# Schematic_of_7_syringe_pump.net
KiCad netlist of a schematic drawn in EAGLE
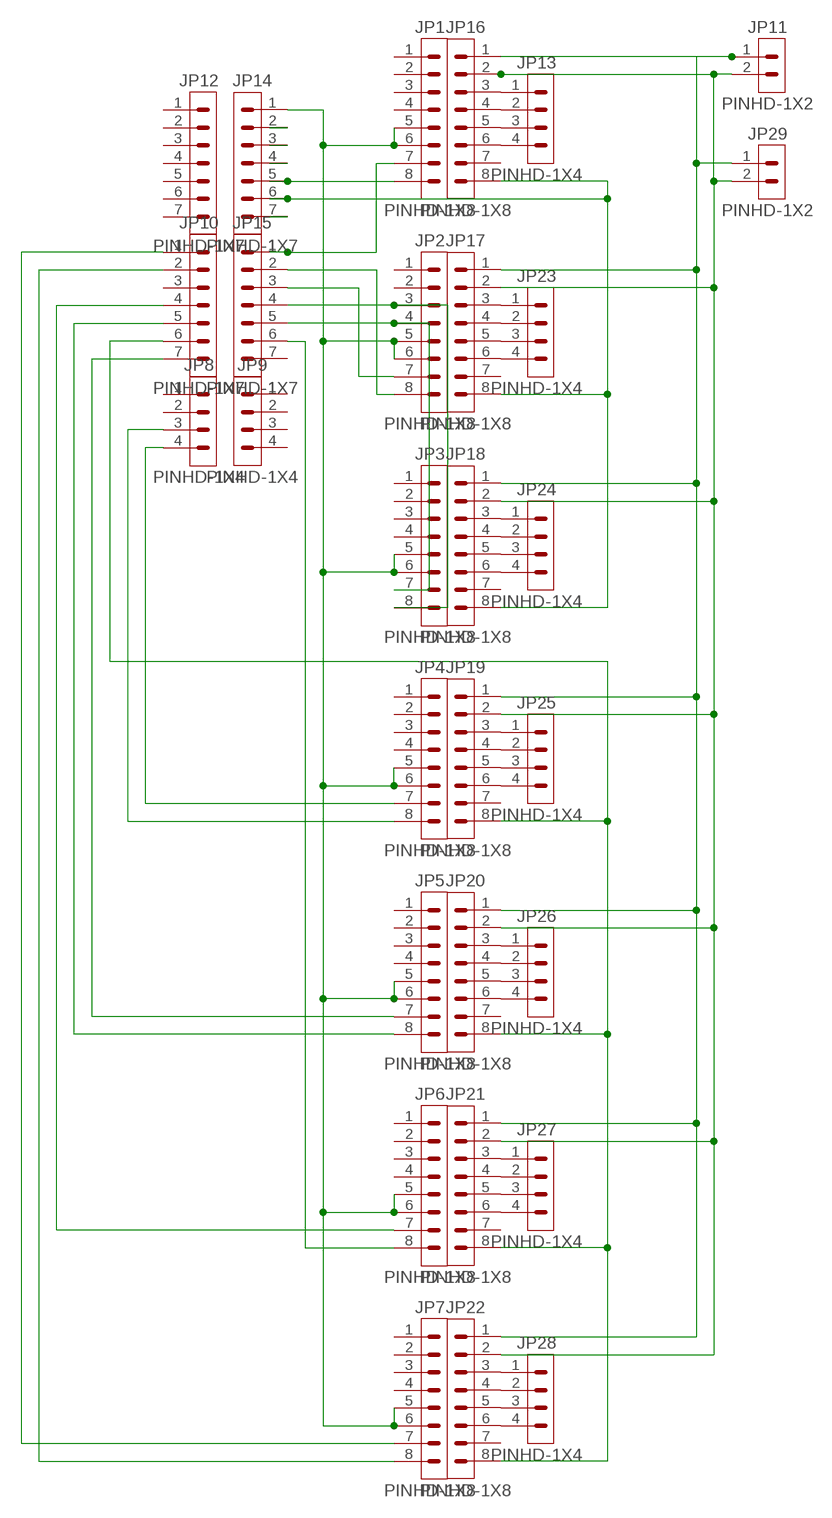
[diagram p0: schematic, sheet 1]

(export (version "E")
  (design (tool "Eeschema 10.0.6"))
  (components
    (comp (ref "JP1")
      (value "PINHD-1X8")
      (footprint "eagle-import:1X08")
      (libsource (lib "eagle-import") (part "PINHD-1X8"))
    )
    (comp (ref "JP2")
      (value "PINHD-1X8")
      (footprint "eagle-import:1X08")
      (libsource (lib "eagle-import") (part "PINHD-1X8"))
    )
    (comp (ref "JP3")
      (value "PINHD-1X8")
      (footprint "eagle-import:1X08")
      (libsource (lib "eagle-import") (part "PINHD-1X8"))
    )
    (comp (ref "JP4")
      (value "PINHD-1X8")
      (footprint "eagle-import:1X08")
      (libsource (lib "eagle-import") (part "PINHD-1X8"))
    )
    (comp (ref "JP5")
      (value "PINHD-1X8")
      (footprint "eagle-import:1X08")
      (libsource (lib "eagle-import") (part "PINHD-1X8"))
    )
    (comp (ref "JP6")
      (value "PINHD-1X8")
      (footprint "eagle-import:1X08")
      (libsource (lib "eagle-import") (part "PINHD-1X8"))
    )
    (comp (ref "JP7")
      (value "PINHD-1X8")
      (footprint "eagle-import:1X08")
      (libsource (lib "eagle-import") (part "PINHD-1X8"))
    )
    (comp (ref "JP8")
      (value "PINHD-1X4")
      (footprint "eagle-import:1X04")
      (libsource (lib "eagle-import") (part "PINHD-1X4"))
    )
    (comp (ref "JP9")
      (value "PINHD-1X4")
      (footprint "eagle-import:1X04")
      (libsource (lib "eagle-import") (part "PINHD-1X4"))
    )
    (comp (ref "JP10")
      (value "PINHD-1X7")
      (footprint "eagle-import:1X07")
      (libsource (lib "eagle-import") (part "PINHD-1X7"))
    )
    (comp (ref "JP11")
      (value "PINHD-1X2")
      (footprint "eagle-import:1X02")
      (libsource (lib "eagle-import") (part "PINHD-1X2"))
    )
    (comp (ref "JP12")
      (value "PINHD-1X7")
      (footprint "eagle-import:1X07")
      (libsource (lib "eagle-import") (part "PINHD-1X7"))
    )
    (comp (ref "JP13")
      (value "PINHD-1X4")
      (footprint "eagle-import:1X04")
      (libsource (lib "eagle-import") (part "PINHD-1X4"))
    )
    (comp (ref "JP14")
      (value "PINHD-1X7")
      (footprint "eagle-import:1X07")
      (libsource (lib "eagle-import") (part "PINHD-1X7"))
    )
    (comp (ref "JP15")
      (value "PINHD-1X7")
      (footprint "eagle-import:1X07")
      (libsource (lib "eagle-import") (part "PINHD-1X7"))
    )
    (comp (ref "JP16")
      (value "PINHD-1X8")
      (footprint "eagle-import:1X08")
      (libsource (lib "eagle-import") (part "PINHD-1X8"))
    )
    (comp (ref "JP17")
      (value "PINHD-1X8")
      (footprint "eagle-import:1X08")
      (libsource (lib "eagle-import") (part "PINHD-1X8"))
    )
    (comp (ref "JP18")
      (value "PINHD-1X8")
      (footprint "eagle-import:1X08")
      (libsource (lib "eagle-import") (part "PINHD-1X8"))
    )
    (comp (ref "JP19")
      (value "PINHD-1X8")
      (footprint "eagle-import:1X08")
      (libsource (lib "eagle-import") (part "PINHD-1X8"))
    )
    (comp (ref "JP20")
      (value "PINHD-1X8")
      (footprint "eagle-import:1X08")
      (libsource (lib "eagle-import") (part "PINHD-1X8"))
    )
    (comp (ref "JP21")
      (value "PINHD-1X8")
      (footprint "eagle-import:1X08")
      (libsource (lib "eagle-import") (part "PINHD-1X8"))
    )
    (comp (ref "JP22")
      (value "PINHD-1X8")
      (footprint "eagle-import:1X08")
      (libsource (lib "eagle-import") (part "PINHD-1X8"))
    )
    (comp (ref "JP23")
      (value "PINHD-1X4")
      (footprint "eagle-import:1X04")
      (libsource (lib "eagle-import") (part "PINHD-1X4"))
    )
    (comp (ref "JP24")
      (value "PINHD-1X4")
      (footprint "eagle-import:1X04")
      (libsource (lib "eagle-import") (part "PINHD-1X4"))
    )
    (comp (ref "JP25")
      (value "PINHD-1X4")
      (footprint "eagle-import:1X04")
      (libsource (lib "eagle-import") (part "PINHD-1X4"))
    )
    (comp (ref "JP26")
      (value "PINHD-1X4")
      (footprint "eagle-import:1X04")
      (libsource (lib "eagle-import") (part "PINHD-1X4"))
    )
    (comp (ref "JP27")
      (value "PINHD-1X4")
      (footprint "eagle-import:1X04")
      (libsource (lib "eagle-import") (part "PINHD-1X4"))
    )
    (comp (ref "JP28")
      (value "PINHD-1X4")
      (footprint "eagle-import:1X04")
      (libsource (lib "eagle-import") (part "PINHD-1X4"))
    )
    (comp (ref "JP29")
      (value "PINHD-1X2")
      (footprint "eagle-import:1X02")
      (libsource (lib "eagle-import") (part "PINHD-1X2"))
    )
  )
  (nets
    (net (code "1") (name "Net-(JP1-Pad5)") (class "Default")
      (node (ref "JP1") (pin "5") (pinfunction "5_5") (pintype "passive"))
      (node (ref "JP1") (pin "6") (pinfunction "6_6") (pintype "passive"))
      (node (ref "JP14") (pin "1") (pinfunction "1_1") (pintype "passive"))
      (node (ref "JP2") (pin "5") (pinfunction "5_5") (pintype "passive"))
      (node (ref "JP2") (pin "6") (pinfunction "6_6") (pintype "passive"))
      (node (ref "JP3") (pin "5") (pinfunction "5_5") (pintype "passive"))
      (node (ref "JP3") (pin "6") (pinfunction "6_6") (pintype "passive"))
      (node (ref "JP4") (pin "5") (pinfunction "5_5") (pintype "passive"))
      (node (ref "JP4") (pin "6") (pinfunction "6_6") (pintype "passive"))
      (node (ref "JP5") (pin "5") (pinfunction "5_5") (pintype "passive"))
      (node (ref "JP5") (pin "6") (pinfunction "6_6") (pintype "passive"))
      (node (ref "JP6") (pin "5") (pinfunction "5_5") (pintype "passive"))
      (node (ref "JP6") (pin "6") (pinfunction "6_6") (pintype "passive"))
      (node (ref "JP7") (pin "5") (pinfunction "5_5") (pintype "passive"))
      (node (ref "JP7") (pin "6") (pinfunction "6_6") (pintype "passive"))
    )
    (net (code "2") (name "Net-(JP1-Pad7)") (class "Default")
      (node (ref "JP1") (pin "7") (pinfunction "7_7") (pintype "passive"))
      (node (ref "JP15") (pin "1") (pinfunction "1_1") (pintype "passive"))
    )
    (net (code "3") (name "Net-(JP1-Pad8)") (class "Default")
      (node (ref "JP1") (pin "8") (pinfunction "8_8") (pintype "passive"))
      (node (ref "JP14") (pin "5") (pinfunction "5_5") (pintype "passive"))
    )
    (net (code "4") (name "Net-(JP4-Pad7)") (class "Default")
      (node (ref "JP4") (pin "7") (pinfunction "7_7") (pintype "passive"))
      (node (ref "JP8") (pin "4") (pinfunction "4_4") (pintype "passive"))
    )
    (net (code "5") (name "Net-(JP4-Pad8)") (class "Default")
      (node (ref "JP4") (pin "8") (pinfunction "8_8") (pintype "passive"))
      (node (ref "JP8") (pin "3") (pinfunction "3_3") (pintype "passive"))
    )
    (net (code "6") (name "Net-(JP10-Pad1)") (class "Default")
      (node (ref "JP10") (pin "1") (pinfunction "1_1") (pintype "passive"))
      (node (ref "JP7") (pin "7") (pinfunction "7_7") (pintype "passive"))
    )
    (net (code "7") (name "Net-(JP10-Pad2)") (class "Default")
      (node (ref "JP10") (pin "2") (pinfunction "2_2") (pintype "passive"))
      (node (ref "JP7") (pin "8") (pinfunction "8_8") (pintype "passive"))
    )
    (net (code "8") (name "Net-(JP10-Pad4)") (class "Default")
      (node (ref "JP10") (pin "4") (pinfunction "4_4") (pintype "passive"))
      (node (ref "JP6") (pin "7") (pinfunction "7_7") (pintype "passive"))
    )
    (net (code "9") (name "Net-(JP10-Pad5)") (class "Default")
      (node (ref "JP10") (pin "5") (pinfunction "5_5") (pintype "passive"))
      (node (ref "JP5") (pin "8") (pinfunction "8_8") (pintype "passive"))
    )
    (net (code "10") (name "Net-(JP10-Pad6)") (class "Default")
      (node (ref "JP10") (pin "6") (pinfunction "6_6") (pintype "passive"))
      (node (ref "JP19") (pin "8") (pinfunction "8_8") (pintype "passive"))
      (node (ref "JP20") (pin "8") (pinfunction "8_8") (pintype "passive"))
      (node (ref "JP21") (pin "8") (pinfunction "8_8") (pintype "passive"))
      (node (ref "JP22") (pin "8") (pinfunction "8_8") (pintype "passive"))
    )
    (net (code "11") (name "Net-(JP10-Pad7)") (class "Default")
      (node (ref "JP10") (pin "7") (pinfunction "7_7") (pintype "passive"))
      (node (ref "JP5") (pin "7") (pinfunction "7_7") (pintype "passive"))
    )
    (net (code "12") (name "Net-(JP11-Pad1)") (class "Default")
      (node (ref "JP11") (pin "1") (pinfunction "1_1") (pintype "passive"))
      (node (ref "JP16") (pin "1") (pinfunction "1_1") (pintype "passive"))
      (node (ref "JP17") (pin "1") (pinfunction "1_1") (pintype "passive"))
      (node (ref "JP18") (pin "1") (pinfunction "1_1") (pintype "passive"))
      (node (ref "JP19") (pin "1") (pinfunction "1_1") (pintype "passive"))
      (node (ref "JP20") (pin "1") (pinfunction "1_1") (pintype "passive"))
      (node (ref "JP21") (pin "1") (pinfunction "1_1") (pintype "passive"))
      (node (ref "JP22") (pin "1") (pinfunction "1_1") (pintype "passive"))
      (node (ref "JP29") (pin "1") (pinfunction "1_1") (pintype "passive"))
    )
    (net (code "13") (name "Net-(JP11-Pad2)") (class "Default")
      (node (ref "JP11") (pin "2") (pinfunction "2_2") (pintype "passive"))
      (node (ref "JP16") (pin "2") (pinfunction "2_2") (pintype "passive"))
      (node (ref "JP17") (pin "2") (pinfunction "2_2") (pintype "passive"))
      (node (ref "JP18") (pin "2") (pinfunction "2_2") (pintype "passive"))
      (node (ref "JP19") (pin "2") (pinfunction "2_2") (pintype "passive"))
      (node (ref "JP20") (pin "2") (pinfunction "2_2") (pintype "passive"))
      (node (ref "JP21") (pin "2") (pinfunction "2_2") (pintype "passive"))
      (node (ref "JP22") (pin "2") (pinfunction "2_2") (pintype "passive"))
      (node (ref "JP29") (pin "2") (pinfunction "2_2") (pintype "passive"))
    )
    (net (code "14") (name "Net-(JP13-Pad1)") (class "Default")
      (node (ref "JP13") (pin "1") (pinfunction "1_1") (pintype "passive"))
      (node (ref "JP16") (pin "3") (pinfunction "3_3") (pintype "passive"))
    )
    (net (code "15") (name "Net-(JP13-Pad2)") (class "Default")
      (node (ref "JP13") (pin "2") (pinfunction "2_2") (pintype "passive"))
      (node (ref "JP16") (pin "4") (pinfunction "4_4") (pintype "passive"))
    )
    (net (code "16") (name "Net-(JP13-Pad3)") (class "Default")
      (node (ref "JP13") (pin "3") (pinfunction "3_3") (pintype "passive"))
      (node (ref "JP16") (pin "5") (pinfunction "5_5") (pintype "passive"))
    )
    (net (code "17") (name "Net-(JP13-Pad4)") (class "Default")
      (node (ref "JP13") (pin "4") (pinfunction "4_4") (pintype "passive"))
      (node (ref "JP16") (pin "6") (pinfunction "6_6") (pintype "passive"))
    )
    (net (code "18") (name "Net-(JP14-Pad6)") (class "Default")
      (node (ref "JP14") (pin "6") (pinfunction "6_6") (pintype "passive"))
      (node (ref "JP16") (pin "8") (pinfunction "8_8") (pintype "passive"))
      (node (ref "JP17") (pin "8") (pinfunction "8_8") (pintype "passive"))
      (node (ref "JP18") (pin "8") (pinfunction "8_8") (pintype "passive"))
    )
    (net (code "19") (name "Net-(JP15-Pad2)") (class "Default")
      (node (ref "JP15") (pin "2") (pinfunction "2_2") (pintype "passive"))
      (node (ref "JP2") (pin "8") (pinfunction "8_8") (pintype "passive"))
    )
    (net (code "20") (name "Net-(JP15-Pad3)") (class "Default")
      (node (ref "JP15") (pin "3") (pinfunction "3_3") (pintype "passive"))
      (node (ref "JP2") (pin "7") (pinfunction "7_7") (pintype "passive"))
    )
    (net (code "21") (name "Net-(JP15-Pad4)") (class "Default")
      (node (ref "JP15") (pin "4") (pinfunction "4_4") (pintype "passive"))
      (node (ref "JP2") (pin "3") (pinfunction "3_3") (pintype "passive"))
      (node (ref "JP3") (pin "8") (pinfunction "8_8") (pintype "passive"))
    )
    (net (code "22") (name "Net-(JP15-Pad5)") (class "Default")
      (node (ref "JP15") (pin "5") (pinfunction "5_5") (pintype "passive"))
      (node (ref "JP2") (pin "4") (pinfunction "4_4") (pintype "passive"))
      (node (ref "JP3") (pin "7") (pinfunction "7_7") (pintype "passive"))
    )
    (net (code "23") (name "Net-(JP15-Pad6)") (class "Default")
      (node (ref "JP15") (pin "6") (pinfunction "6_6") (pintype "passive"))
      (node (ref "JP6") (pin "8") (pinfunction "8_8") (pintype "passive"))
    )
    (net (code "24") (name "Net-(JP17-Pad3)") (class "Default")
      (node (ref "JP17") (pin "3") (pinfunction "3_3") (pintype "passive"))
      (node (ref "JP23") (pin "1") (pinfunction "1_1") (pintype "passive"))
    )
    (net (code "25") (name "Net-(JP17-Pad4)") (class "Default")
      (node (ref "JP17") (pin "4") (pinfunction "4_4") (pintype "passive"))
      (node (ref "JP23") (pin "2") (pinfunction "2_2") (pintype "passive"))
    )
    (net (code "26") (name "Net-(JP17-Pad5)") (class "Default")
      (node (ref "JP17") (pin "5") (pinfunction "5_5") (pintype "passive"))
      (node (ref "JP23") (pin "3") (pinfunction "3_3") (pintype "passive"))
    )
    (net (code "27") (name "Net-(JP17-Pad6)") (class "Default")
      (node (ref "JP17") (pin "6") (pinfunction "6_6") (pintype "passive"))
      (node (ref "JP23") (pin "4") (pinfunction "4_4") (pintype "passive"))
    )
    (net (code "28") (name "Net-(JP18-Pad3)") (class "Default")
      (node (ref "JP18") (pin "3") (pinfunction "3_3") (pintype "passive"))
      (node (ref "JP24") (pin "1") (pinfunction "1_1") (pintype "passive"))
    )
    (net (code "29") (name "Net-(JP18-Pad4)") (class "Default")
      (node (ref "JP18") (pin "4") (pinfunction "4_4") (pintype "passive"))
      (node (ref "JP24") (pin "2") (pinfunction "2_2") (pintype "passive"))
    )
    (net (code "30") (name "Net-(JP18-Pad5)") (class "Default")
      (node (ref "JP18") (pin "5") (pinfunction "5_5") (pintype "passive"))
      (node (ref "JP24") (pin "3") (pinfunction "3_3") (pintype "passive"))
    )
    (net (code "31") (name "Net-(JP18-Pad6)") (class "Default")
      (node (ref "JP18") (pin "6") (pinfunction "6_6") (pintype "passive"))
      (node (ref "JP24") (pin "4") (pinfunction "4_4") (pintype "passive"))
    )
    (net (code "32") (name "Net-(JP19-Pad3)") (class "Default")
      (node (ref "JP19") (pin "3") (pinfunction "3_3") (pintype "passive"))
      (node (ref "JP25") (pin "1") (pinfunction "1_1") (pintype "passive"))
    )
    (net (code "33") (name "Net-(JP19-Pad4)") (class "Default")
      (node (ref "JP19") (pin "4") (pinfunction "4_4") (pintype "passive"))
      (node (ref "JP25") (pin "2") (pinfunction "2_2") (pintype "passive"))
    )
    (net (code "34") (name "Net-(JP19-Pad5)") (class "Default")
      (node (ref "JP19") (pin "5") (pinfunction "5_5") (pintype "passive"))
      (node (ref "JP25") (pin "3") (pinfunction "3_3") (pintype "passive"))
    )
    (net (code "35") (name "Net-(JP19-Pad6)") (class "Default")
      (node (ref "JP19") (pin "6") (pinfunction "6_6") (pintype "passive"))
      (node (ref "JP25") (pin "4") (pinfunction "4_4") (pintype "passive"))
    )
    (net (code "36") (name "Net-(JP20-Pad3)") (class "Default")
      (node (ref "JP20") (pin "3") (pinfunction "3_3") (pintype "passive"))
      (node (ref "JP26") (pin "1") (pinfunction "1_1") (pintype "passive"))
    )
    (net (code "37") (name "Net-(JP20-Pad4)") (class "Default")
      (node (ref "JP20") (pin "4") (pinfunction "4_4") (pintype "passive"))
      (node (ref "JP26") (pin "2") (pinfunction "2_2") (pintype "passive"))
    )
    (net (code "38") (name "Net-(JP20-Pad5)") (class "Default")
      (node (ref "JP20") (pin "5") (pinfunction "5_5") (pintype "passive"))
      (node (ref "JP26") (pin "3") (pinfunction "3_3") (pintype "passive"))
    )
    (net (code "39") (name "Net-(JP20-Pad6)") (class "Default")
      (node (ref "JP20") (pin "6") (pinfunction "6_6") (pintype "passive"))
      (node (ref "JP26") (pin "4") (pinfunction "4_4") (pintype "passive"))
    )
    (net (code "40") (name "Net-(JP21-Pad3)") (class "Default")
      (node (ref "JP21") (pin "3") (pinfunction "3_3") (pintype "passive"))
      (node (ref "JP27") (pin "1") (pinfunction "1_1") (pintype "passive"))
    )
    (net (code "41") (name "Net-(JP21-Pad4)") (class "Default")
      (node (ref "JP21") (pin "4") (pinfunction "4_4") (pintype "passive"))
      (node (ref "JP27") (pin "2") (pinfunction "2_2") (pintype "passive"))
    )
    (net (code "42") (name "Net-(JP21-Pad5)") (class "Default")
      (node (ref "JP21") (pin "5") (pinfunction "5_5") (pintype "passive"))
      (node (ref "JP27") (pin "3") (pinfunction "3_3") (pintype "passive"))
    )
    (net (code "43") (name "Net-(JP21-Pad6)") (class "Default")
      (node (ref "JP21") (pin "6") (pinfunction "6_6") (pintype "passive"))
      (node (ref "JP27") (pin "4") (pinfunction "4_4") (pintype "passive"))
    )
    (net (code "44") (name "Net-(JP22-Pad3)") (class "Default")
      (node (ref "JP22") (pin "3") (pinfunction "3_3") (pintype "passive"))
      (node (ref "JP28") (pin "1") (pinfunction "1_1") (pintype "passive"))
    )
    (net (code "45") (name "Net-(JP22-Pad4)") (class "Default")
      (node (ref "JP22") (pin "4") (pinfunction "4_4") (pintype "passive"))
      (node (ref "JP28") (pin "2") (pinfunction "2_2") (pintype "passive"))
    )
    (net (code "46") (name "Net-(JP22-Pad5)") (class "Default")
      (node (ref "JP22") (pin "5") (pinfunction "5_5") (pintype "passive"))
      (node (ref "JP28") (pin "3") (pinfunction "3_3") (pintype "passive"))
    )
    (net (code "47") (name "Net-(JP22-Pad6)") (class "Default")
      (node (ref "JP22") (pin "6") (pinfunction "6_6") (pintype "passive"))
      (node (ref "JP28") (pin "4") (pinfunction "4_4") (pintype "passive"))
    )
    (net (code "48") (name "unconnected-(JP1-Pad1)") (class "Default")
      (node (ref "JP1") (pin "1") (pinfunction "1_1") (pintype "passive"))
    )
    (net (code "49") (name "unconnected-(JP1-Pad2)") (class "Default")
      (node (ref "JP1") (pin "2") (pinfunction "2_2") (pintype "passive"))
    )
    (net (code "50") (name "unconnected-(JP1-Pad3)") (class "Default")
      (node (ref "JP1") (pin "3") (pinfunction "3_3") (pintype "passive"))
    )
    (net (code "51") (name "unconnected-(JP1-Pad4)") (class "Default")
      (node (ref "JP1") (pin "4") (pinfunction "4_4") (pintype "passive"))
    )
    (net (code "52") (name "unconnected-(JP2-Pad1)") (class "Default")
      (node (ref "JP2") (pin "1") (pinfunction "1_1") (pintype "passive"))
    )
    (net (code "53") (name "unconnected-(JP2-Pad2)") (class "Default")
      (node (ref "JP2") (pin "2") (pinfunction "2_2") (pintype "passive"))
    )
    (net (code "54") (name "unconnected-(JP3-Pad1)") (class "Default")
      (node (ref "JP3") (pin "1") (pinfunction "1_1") (pintype "passive"))
    )
    (net (code "55") (name "unconnected-(JP3-Pad2)") (class "Default")
      (node (ref "JP3") (pin "2") (pinfunction "2_2") (pintype "passive"))
    )
    (net (code "56") (name "unconnected-(JP3-Pad3)") (class "Default")
      (node (ref "JP3") (pin "3") (pinfunction "3_3") (pintype "passive"))
    )
    (net (code "57") (name "unconnected-(JP3-Pad4)") (class "Default")
      (node (ref "JP3") (pin "4") (pinfunction "4_4") (pintype "passive"))
    )
    (net (code "58") (name "unconnected-(JP4-Pad1)") (class "Default")
      (node (ref "JP4") (pin "1") (pinfunction "1_1") (pintype "passive"))
    )
    (net (code "59") (name "unconnected-(JP4-Pad2)") (class "Default")
      (node (ref "JP4") (pin "2") (pinfunction "2_2") (pintype "passive"))
    )
    (net (code "60") (name "unconnected-(JP4-Pad3)") (class "Default")
      (node (ref "JP4") (pin "3") (pinfunction "3_3") (pintype "passive"))
    )
    (net (code "61") (name "unconnected-(JP4-Pad4)") (class "Default")
      (node (ref "JP4") (pin "4") (pinfunction "4_4") (pintype "passive"))
    )
    (net (code "62") (name "unconnected-(JP5-Pad1)") (class "Default")
      (node (ref "JP5") (pin "1") (pinfunction "1_1") (pintype "passive"))
    )
    (net (code "63") (name "unconnected-(JP5-Pad2)") (class "Default")
      (node (ref "JP5") (pin "2") (pinfunction "2_2") (pintype "passive"))
    )
    (net (code "64") (name "unconnected-(JP5-Pad3)") (class "Default")
      (node (ref "JP5") (pin "3") (pinfunction "3_3") (pintype "passive"))
    )
    (net (code "65") (name "unconnected-(JP5-Pad4)") (class "Default")
      (node (ref "JP5") (pin "4") (pinfunction "4_4") (pintype "passive"))
    )
    (net (code "66") (name "unconnected-(JP6-Pad1)") (class "Default")
      (node (ref "JP6") (pin "1") (pinfunction "1_1") (pintype "passive"))
    )
    (net (code "67") (name "unconnected-(JP6-Pad2)") (class "Default")
      (node (ref "JP6") (pin "2") (pinfunction "2_2") (pintype "passive"))
    )
    (net (code "68") (name "unconnected-(JP6-Pad3)") (class "Default")
      (node (ref "JP6") (pin "3") (pinfunction "3_3") (pintype "passive"))
    )
    (net (code "69") (name "unconnected-(JP6-Pad4)") (class "Default")
      (node (ref "JP6") (pin "4") (pinfunction "4_4") (pintype "passive"))
    )
    (net (code "70") (name "unconnected-(JP7-Pad1)") (class "Default")
      (node (ref "JP7") (pin "1") (pinfunction "1_1") (pintype "passive"))
    )
    (net (code "71") (name "unconnected-(JP7-Pad2)") (class "Default")
      (node (ref "JP7") (pin "2") (pinfunction "2_2") (pintype "passive"))
    )
    (net (code "72") (name "unconnected-(JP7-Pad3)") (class "Default")
      (node (ref "JP7") (pin "3") (pinfunction "3_3") (pintype "passive"))
    )
    (net (code "73") (name "unconnected-(JP7-Pad4)") (class "Default")
      (node (ref "JP7") (pin "4") (pinfunction "4_4") (pintype "passive"))
    )
    (net (code "74") (name "unconnected-(JP8-Pad1)") (class "Default")
      (node (ref "JP8") (pin "1") (pinfunction "1_1") (pintype "passive"))
    )
    (net (code "75") (name "unconnected-(JP8-Pad2)") (class "Default")
      (node (ref "JP8") (pin "2") (pinfunction "2_2") (pintype "passive"))
    )
    (net (code "76") (name "unconnected-(JP9-Pad1)") (class "Default")
      (node (ref "JP9") (pin "1") (pinfunction "1_1") (pintype "passive"))
    )
    (net (code "77") (name "unconnected-(JP9-Pad2)") (class "Default")
      (node (ref "JP9") (pin "2") (pinfunction "2_2") (pintype "passive"))
    )
    (net (code "78") (name "unconnected-(JP9-Pad3)") (class "Default")
      (node (ref "JP9") (pin "3") (pinfunction "3_3") (pintype "passive"))
    )
    (net (code "79") (name "unconnected-(JP9-Pad4)") (class "Default")
      (node (ref "JP9") (pin "4") (pinfunction "4_4") (pintype "passive"))
    )
    (net (code "80") (name "unconnected-(JP10-Pad3)") (class "Default")
      (node (ref "JP10") (pin "3") (pinfunction "3_3") (pintype "passive"))
    )
    (net (code "81") (name "unconnected-(JP12-Pad1)") (class "Default")
      (node (ref "JP12") (pin "1") (pinfunction "1_1") (pintype "passive"))
    )
    (net (code "82") (name "unconnected-(JP12-Pad2)") (class "Default")
      (node (ref "JP12") (pin "2") (pinfunction "2_2") (pintype "passive"))
    )
    (net (code "83") (name "unconnected-(JP12-Pad3)") (class "Default")
      (node (ref "JP12") (pin "3") (pinfunction "3_3") (pintype "passive"))
    )
    (net (code "84") (name "unconnected-(JP12-Pad4)") (class "Default")
      (node (ref "JP12") (pin "4") (pinfunction "4_4") (pintype "passive"))
    )
    (net (code "85") (name "unconnected-(JP12-Pad5)") (class "Default")
      (node (ref "JP12") (pin "5") (pinfunction "5_5") (pintype "passive"))
    )
    (net (code "86") (name "unconnected-(JP12-Pad6)") (class "Default")
      (node (ref "JP12") (pin "6") (pinfunction "6_6") (pintype "passive"))
    )
    (net (code "87") (name "unconnected-(JP12-Pad7)") (class "Default")
      (node (ref "JP12") (pin "7") (pinfunction "7_7") (pintype "passive"))
    )
    (net (code "88") (name "unconnected-(JP14-Pad2)") (class "Default")
      (node (ref "JP14") (pin "2") (pinfunction "2_2") (pintype "passive"))
    )
    (net (code "89") (name "unconnected-(JP14-Pad3)") (class "Default")
      (node (ref "JP14") (pin "3") (pinfunction "3_3") (pintype "passive"))
    )
    (net (code "90") (name "unconnected-(JP14-Pad4)") (class "Default")
      (node (ref "JP14") (pin "4") (pinfunction "4_4") (pintype "passive"))
    )
    (net (code "91") (name "unconnected-(JP14-Pad7)") (class "Default")
      (node (ref "JP14") (pin "7") (pinfunction "7_7") (pintype "passive"))
    )
    (net (code "92") (name "unconnected-(JP15-Pad7)") (class "Default")
      (node (ref "JP15") (pin "7") (pinfunction "7_7") (pintype "passive"))
    )
    (net (code "93") (name "unconnected-(JP16-Pad7)") (class "Default")
      (node (ref "JP16") (pin "7") (pinfunction "7_7") (pintype "passive"))
    )
    (net (code "94") (name "unconnected-(JP17-Pad7)") (class "Default")
      (node (ref "JP17") (pin "7") (pinfunction "7_7") (pintype "passive"))
    )
    (net (code "95") (name "unconnected-(JP18-Pad7)") (class "Default")
      (node (ref "JP18") (pin "7") (pinfunction "7_7") (pintype "passive"))
    )
    (net (code "96") (name "unconnected-(JP19-Pad7)") (class "Default")
      (node (ref "JP19") (pin "7") (pinfunction "7_7") (pintype "passive"))
    )
    (net (code "97") (name "unconnected-(JP20-Pad7)") (class "Default")
      (node (ref "JP20") (pin "7") (pinfunction "7_7") (pintype "passive"))
    )
    (net (code "98") (name "unconnected-(JP21-Pad7)") (class "Default")
      (node (ref "JP21") (pin "7") (pinfunction "7_7") (pintype "passive"))
    )
    (net (code "99") (name "unconnected-(JP22-Pad7)") (class "Default")
      (node (ref "JP22") (pin "7") (pinfunction "7_7") (pintype "passive"))
    )
  )
)
